# pms.net
KiCad netlist of a schematic drawn in EAGLE
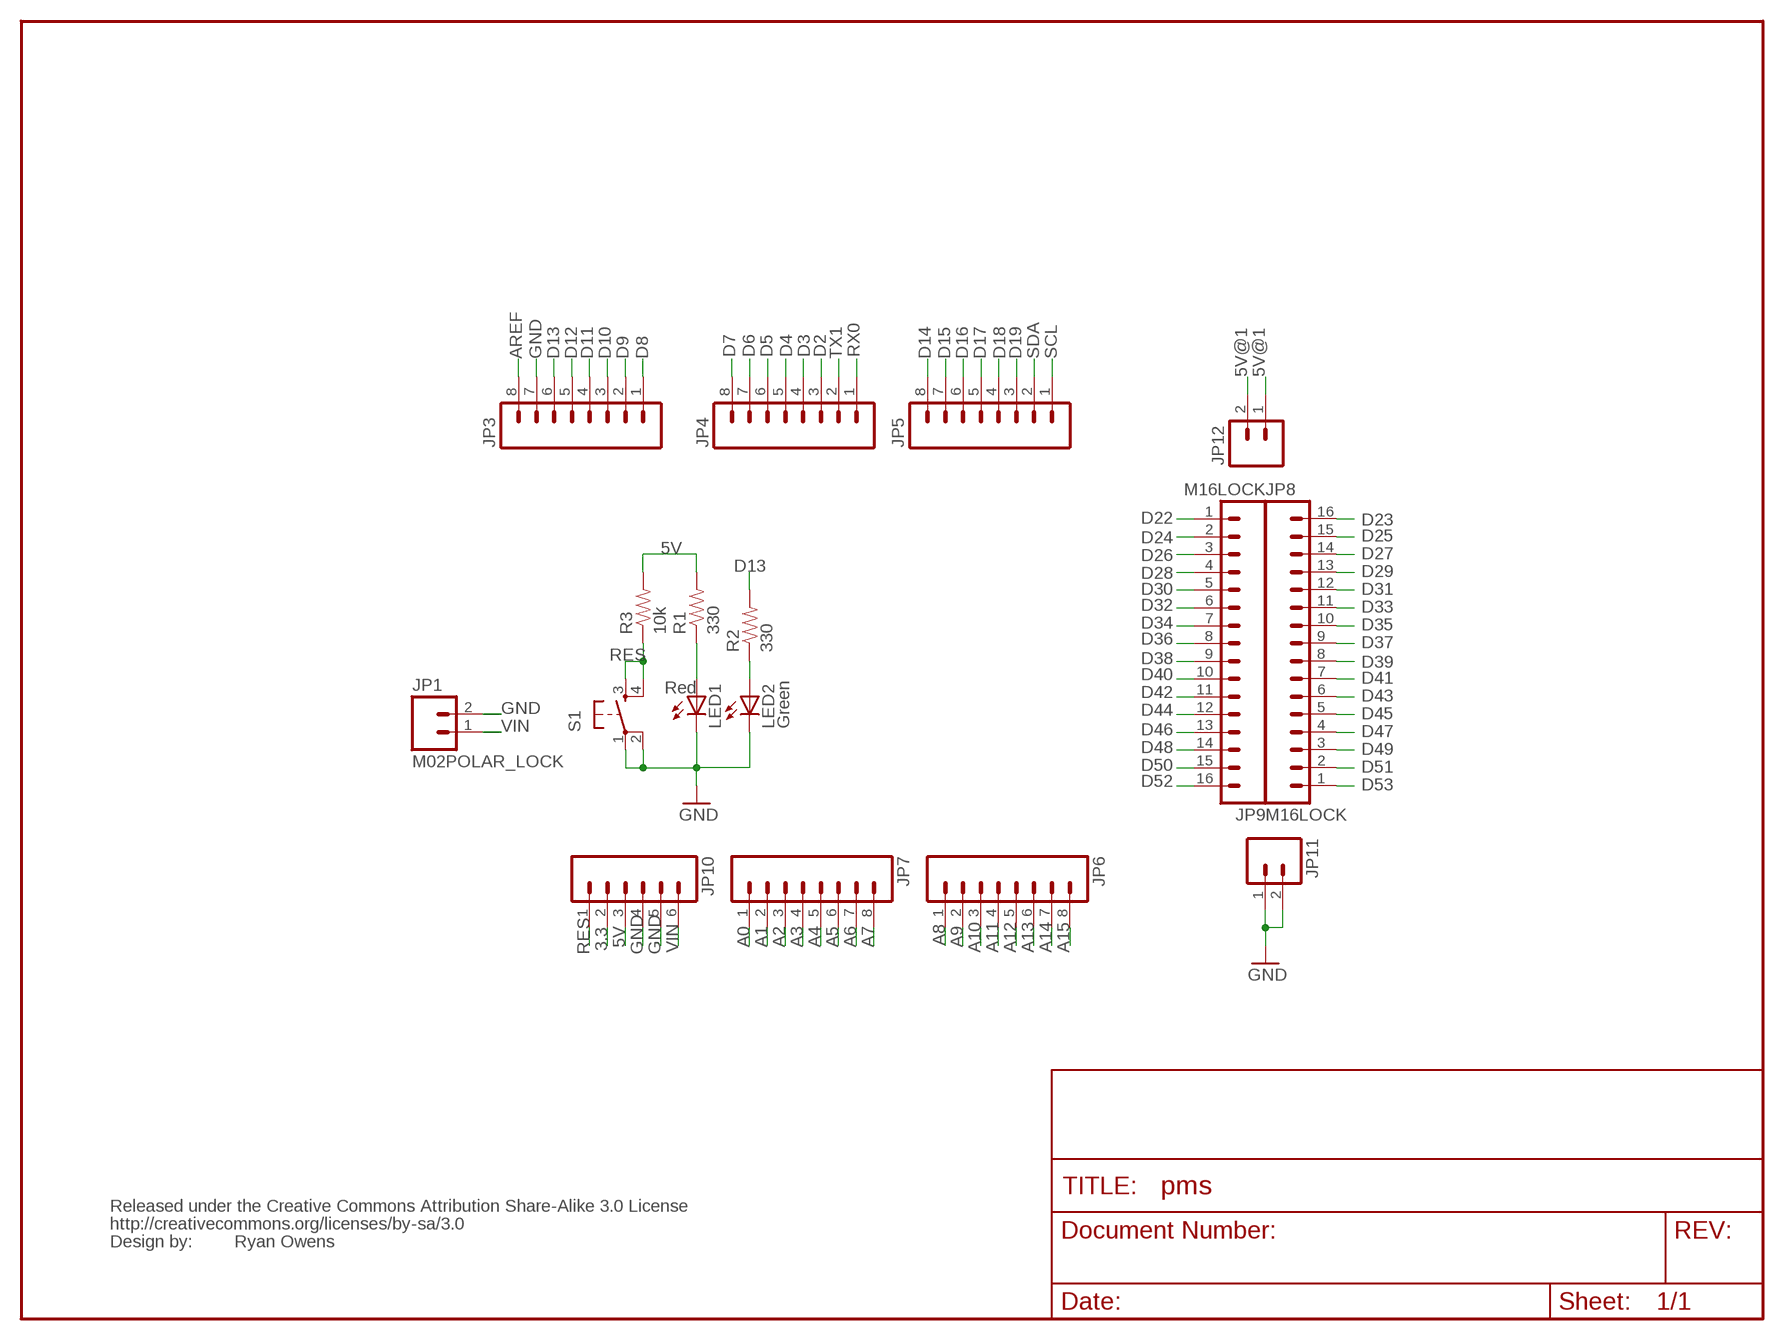
[diagram p0: schematic, sheet 1]

(export (version "E")
  (design (tool "Eeschema 10.0.6"))
  (components
    (comp (ref "JP1")
      (value "M02POLAR_LOCK")
      (footprint "eagle-import:MOLEX-1X2_LOCK")
      (libsource (lib "eagle-import") (part "SparkFun-Connectors_M02POLAR_LOCK"))
    )
    (comp (ref "JP3")
      (value "M08LOCK")
      (footprint "eagle-import:1X08_LOCK")
      (libsource (lib "eagle-import") (part "M08LOCK"))
    )
    (comp (ref "JP4")
      (value "M08LOCK")
      (footprint "eagle-import:1X08_LOCK")
      (libsource (lib "eagle-import") (part "M08LOCK"))
    )
    (comp (ref "JP5")
      (value "M08LOCK")
      (footprint "eagle-import:1X08_LOCK")
      (libsource (lib "eagle-import") (part "M08LOCK"))
    )
    (comp (ref "JP6")
      (value "M08LOCK")
      (footprint "eagle-import:1X08_LOCK")
      (libsource (lib "eagle-import") (part "M08LOCK"))
    )
    (comp (ref "JP7")
      (value "M08LOCK")
      (footprint "eagle-import:1X08_LOCK")
      (libsource (lib "eagle-import") (part "M08LOCK"))
    )
    (comp (ref "JP8")
      (value "M16LOCK")
      (footprint "eagle-import:1X16_LOCK")
      (libsource (lib "eagle-import") (part "M16LOCK"))
    )
    (comp (ref "JP9")
      (value "M16LOCK")
      (footprint "eagle-import:1X16_LOCK")
      (libsource (lib "eagle-import") (part "M16LOCK"))
    )
    (comp (ref "JP10")
      (value "M06LOCK")
      (footprint "eagle-import:1X06_LOCK")
      (libsource (lib "eagle-import") (part "M06LOCK"))
    )
    (comp (ref "JP11")
      (value "M02LOCK")
      (footprint "eagle-import:1X02_LOCK")
      (libsource (lib "eagle-import") (part "M02LOCK"))
    )
    (comp (ref "JP12")
      (value "M02LOCK")
      (footprint "eagle-import:1X02_LOCK")
      (libsource (lib "eagle-import") (part "M02LOCK"))
    )
    (comp (ref "LED1")
      (value "Red")
      (footprint "eagle-import:LED5MM")
      (libsource (lib "eagle-import") (part "LED5MM"))
    )
    (comp (ref "LED2")
      (value "Green")
      (footprint "eagle-import:LED5MM")
      (libsource (lib "eagle-import") (part "LED5MM"))
    )
    (comp (ref "R1")
      (value "330")
      (footprint "eagle-import:AXIAL-0.3")
      (libsource (lib "eagle-import") (part "RESISTORPTH1"))
    )
    (comp (ref "R2")
      (value "330")
      (footprint "eagle-import:AXIAL-0.3")
      (libsource (lib "eagle-import") (part "RESISTORPTH1"))
    )
    (comp (ref "R3")
      (value "10k")
      (footprint "eagle-import:AXIAL-0.3")
      (libsource (lib "eagle-import") (part "RESISTORPTH1"))
    )
    (comp (ref "S1")
      (value "TAC_SWITCHPTH")
      (footprint "eagle-import:TACTILE-PTH")
      (libsource (lib "eagle-import") (part "TAC_SWITCHPTH"))
    )
    (comp (ref "U$2")
      (value "CREATIVE_COMMONS")
      (footprint "eagle-import:CREATIVE_COMMONS")
      (libsource (lib "eagle-import") (part "CREATIVE_COMMONS"))
    )
  )
  (nets
    (net (code "1") (name "/3.3") (class "Default")
      (node (ref "JP10") (pin "2") (pinfunction "2_2") (pintype "passive"))
    )
    (net (code "2") (name "/5V") (class "Default")
      (node (ref "JP10") (pin "3") (pinfunction "3_3") (pintype "passive"))
      (node (ref "R1") (pin "P$2") (pinfunction "2_P$2") (pintype "passive"))
      (node (ref "R3") (pin "P$2") (pinfunction "2_P$2") (pintype "passive"))
    )
    (net (code "3") (name "/5V@1") (class "Default")
      (node (ref "JP12") (pin "1") (pinfunction "1_1") (pintype "passive"))
      (node (ref "JP12") (pin "2") (pinfunction "2_2") (pintype "passive"))
    )
    (net (code "4") (name "/A0") (class "Default")
      (node (ref "JP7") (pin "1") (pinfunction "1_1") (pintype "passive"))
    )
    (net (code "5") (name "/A1") (class "Default")
      (node (ref "JP7") (pin "2") (pinfunction "2_2") (pintype "passive"))
    )
    (net (code "6") (name "/A2") (class "Default")
      (node (ref "JP7") (pin "3") (pinfunction "3_3") (pintype "passive"))
    )
    (net (code "7") (name "/A3") (class "Default")
      (node (ref "JP7") (pin "4") (pinfunction "4_4") (pintype "passive"))
    )
    (net (code "8") (name "/A4") (class "Default")
      (node (ref "JP7") (pin "5") (pinfunction "5_5") (pintype "passive"))
    )
    (net (code "9") (name "/A5") (class "Default")
      (node (ref "JP7") (pin "6") (pinfunction "6_6") (pintype "passive"))
    )
    (net (code "10") (name "/A6") (class "Default")
      (node (ref "JP7") (pin "7") (pinfunction "7_7") (pintype "passive"))
    )
    (net (code "11") (name "/A7") (class "Default")
      (node (ref "JP7") (pin "8") (pinfunction "8_8") (pintype "passive"))
    )
    (net (code "12") (name "/A8") (class "Default")
      (node (ref "JP6") (pin "1") (pinfunction "1_1") (pintype "passive"))
    )
    (net (code "13") (name "/A9") (class "Default")
      (node (ref "JP6") (pin "2") (pinfunction "2_2") (pintype "passive"))
    )
    (net (code "14") (name "/A10") (class "Default")
      (node (ref "JP6") (pin "3") (pinfunction "3_3") (pintype "passive"))
    )
    (net (code "15") (name "/A11") (class "Default")
      (node (ref "JP6") (pin "4") (pinfunction "4_4") (pintype "passive"))
    )
    (net (code "16") (name "/A12") (class "Default")
      (node (ref "JP6") (pin "5") (pinfunction "5_5") (pintype "passive"))
    )
    (net (code "17") (name "/A13") (class "Default")
      (node (ref "JP6") (pin "6") (pinfunction "6_6") (pintype "passive"))
    )
    (net (code "18") (name "/A14") (class "Default")
      (node (ref "JP6") (pin "7") (pinfunction "7_7") (pintype "passive"))
    )
    (net (code "19") (name "/A15") (class "Default")
      (node (ref "JP6") (pin "8") (pinfunction "8_8") (pintype "passive"))
    )
    (net (code "20") (name "/AREF") (class "Default")
      (node (ref "JP3") (pin "8") (pinfunction "8_8") (pintype "passive"))
    )
    (net (code "21") (name "/D2") (class "Default")
      (node (ref "JP4") (pin "3") (pinfunction "3_3") (pintype "passive"))
    )
    (net (code "22") (name "/D3") (class "Default")
      (node (ref "JP4") (pin "4") (pinfunction "4_4") (pintype "passive"))
    )
    (net (code "23") (name "/D4") (class "Default")
      (node (ref "JP4") (pin "5") (pinfunction "5_5") (pintype "passive"))
    )
    (net (code "24") (name "/D5") (class "Default")
      (node (ref "JP4") (pin "6") (pinfunction "6_6") (pintype "passive"))
    )
    (net (code "25") (name "/D6") (class "Default")
      (node (ref "JP4") (pin "7") (pinfunction "7_7") (pintype "passive"))
    )
    (net (code "26") (name "/D7") (class "Default")
      (node (ref "JP4") (pin "8") (pinfunction "8_8") (pintype "passive"))
    )
    (net (code "27") (name "/D8") (class "Default")
      (node (ref "JP3") (pin "1") (pinfunction "1_1") (pintype "passive"))
    )
    (net (code "28") (name "/D9") (class "Default")
      (node (ref "JP3") (pin "2") (pinfunction "2_2") (pintype "passive"))
    )
    (net (code "29") (name "/D10") (class "Default")
      (node (ref "JP3") (pin "3") (pinfunction "3_3") (pintype "passive"))
    )
    (net (code "30") (name "/D11") (class "Default")
      (node (ref "JP3") (pin "4") (pinfunction "4_4") (pintype "passive"))
    )
    (net (code "31") (name "/D12") (class "Default")
      (node (ref "JP3") (pin "5") (pinfunction "5_5") (pintype "passive"))
    )
    (net (code "32") (name "/D13") (class "Default")
      (node (ref "JP3") (pin "6") (pinfunction "6_6") (pintype "passive"))
      (node (ref "R2") (pin "P$2") (pinfunction "2_P$2") (pintype "passive"))
    )
    (net (code "33") (name "/D14") (class "Default")
      (node (ref "JP5") (pin "8") (pinfunction "8_8") (pintype "passive"))
    )
    (net (code "34") (name "/D15") (class "Default")
      (node (ref "JP5") (pin "7") (pinfunction "7_7") (pintype "passive"))
    )
    (net (code "35") (name "/D16") (class "Default")
      (node (ref "JP5") (pin "6") (pinfunction "6_6") (pintype "passive"))
    )
    (net (code "36") (name "/D17") (class "Default")
      (node (ref "JP5") (pin "5") (pinfunction "5_5") (pintype "passive"))
    )
    (net (code "37") (name "/D18") (class "Default")
      (node (ref "JP5") (pin "4") (pinfunction "4_4") (pintype "passive"))
    )
    (net (code "38") (name "/D19") (class "Default")
      (node (ref "JP5") (pin "3") (pinfunction "3_3") (pintype "passive"))
    )
    (net (code "39") (name "/D22") (class "Default")
      (node (ref "JP9") (pin "1") (pinfunction "1_1") (pintype "passive"))
    )
    (net (code "40") (name "/D23") (class "Default")
      (node (ref "JP8") (pin "16") (pinfunction "16_16") (pintype "passive"))
    )
    (net (code "41") (name "/D24") (class "Default")
      (node (ref "JP9") (pin "2") (pinfunction "2_2") (pintype "passive"))
    )
    (net (code "42") (name "/D25") (class "Default")
      (node (ref "JP8") (pin "15") (pinfunction "15_15") (pintype "passive"))
    )
    (net (code "43") (name "/D26") (class "Default")
      (node (ref "JP9") (pin "3") (pinfunction "3_3") (pintype "passive"))
    )
    (net (code "44") (name "/D27") (class "Default")
      (node (ref "JP8") (pin "14") (pinfunction "14_14") (pintype "passive"))
    )
    (net (code "45") (name "/D28") (class "Default")
      (node (ref "JP9") (pin "4") (pinfunction "4_4") (pintype "passive"))
    )
    (net (code "46") (name "/D29") (class "Default")
      (node (ref "JP8") (pin "13") (pinfunction "13_13") (pintype "passive"))
    )
    (net (code "47") (name "/D30") (class "Default")
      (node (ref "JP9") (pin "5") (pinfunction "5_5") (pintype "passive"))
    )
    (net (code "48") (name "/D31") (class "Default")
      (node (ref "JP8") (pin "12") (pinfunction "12_12") (pintype "passive"))
    )
    (net (code "49") (name "/D32") (class "Default")
      (node (ref "JP9") (pin "6") (pinfunction "6_6") (pintype "passive"))
    )
    (net (code "50") (name "/D33") (class "Default")
      (node (ref "JP8") (pin "11") (pinfunction "11_11") (pintype "passive"))
    )
    (net (code "51") (name "/D34") (class "Default")
      (node (ref "JP9") (pin "7") (pinfunction "7_7") (pintype "passive"))
    )
    (net (code "52") (name "/D35") (class "Default")
      (node (ref "JP8") (pin "10") (pinfunction "10_10") (pintype "passive"))
    )
    (net (code "53") (name "/D36") (class "Default")
      (node (ref "JP9") (pin "8") (pinfunction "8_8") (pintype "passive"))
    )
    (net (code "54") (name "/D37") (class "Default")
      (node (ref "JP8") (pin "9") (pinfunction "9_9") (pintype "passive"))
    )
    (net (code "55") (name "/D38") (class "Default")
      (node (ref "JP9") (pin "9") (pinfunction "9_9") (pintype "passive"))
    )
    (net (code "56") (name "/D39") (class "Default")
      (node (ref "JP8") (pin "8") (pinfunction "8_8") (pintype "passive"))
    )
    (net (code "57") (name "/D40") (class "Default")
      (node (ref "JP9") (pin "10") (pinfunction "10_10") (pintype "passive"))
    )
    (net (code "58") (name "/D41") (class "Default")
      (node (ref "JP8") (pin "7") (pinfunction "7_7") (pintype "passive"))
    )
    (net (code "59") (name "/D42") (class "Default")
      (node (ref "JP9") (pin "11") (pinfunction "11_11") (pintype "passive"))
    )
    (net (code "60") (name "/D43") (class "Default")
      (node (ref "JP8") (pin "6") (pinfunction "6_6") (pintype "passive"))
    )
    (net (code "61") (name "/D44") (class "Default")
      (node (ref "JP9") (pin "12") (pinfunction "12_12") (pintype "passive"))
    )
    (net (code "62") (name "/D45") (class "Default")
      (node (ref "JP8") (pin "5") (pinfunction "5_5") (pintype "passive"))
    )
    (net (code "63") (name "/D46") (class "Default")
      (node (ref "JP9") (pin "13") (pinfunction "13_13") (pintype "passive"))
    )
    (net (code "64") (name "/D47") (class "Default")
      (node (ref "JP8") (pin "4") (pinfunction "4_4") (pintype "passive"))
    )
    (net (code "65") (name "/D48") (class "Default")
      (node (ref "JP9") (pin "14") (pinfunction "14_14") (pintype "passive"))
    )
    (net (code "66") (name "/D49") (class "Default")
      (node (ref "JP8") (pin "3") (pinfunction "3_3") (pintype "passive"))
    )
    (net (code "67") (name "/D50") (class "Default")
      (node (ref "JP9") (pin "15") (pinfunction "15_15") (pintype "passive"))
    )
    (net (code "68") (name "/D51") (class "Default")
      (node (ref "JP8") (pin "2") (pinfunction "2_2") (pintype "passive"))
    )
    (net (code "69") (name "/D52") (class "Default")
      (node (ref "JP9") (pin "16") (pinfunction "16_16") (pintype "passive"))
    )
    (net (code "70") (name "/D53") (class "Default")
      (node (ref "JP8") (pin "1") (pinfunction "1_1") (pintype "passive"))
    )
    (net (code "71") (name "/RES") (class "Default")
      (node (ref "JP10") (pin "1") (pinfunction "1_1") (pintype "passive"))
      (node (ref "R3") (pin "P$1") (pinfunction "1_P$1") (pintype "passive"))
      (node (ref "S1") (pin "3") (pinfunction "3_3") (pintype "passive"))
      (node (ref "S1") (pin "4") (pinfunction "4_4") (pintype "passive"))
    )
    (net (code "72") (name "/RX0") (class "Default")
      (node (ref "JP4") (pin "1") (pinfunction "1_1") (pintype "passive"))
    )
    (net (code "73") (name "/SCL") (class "Default")
      (node (ref "JP5") (pin "1") (pinfunction "1_1") (pintype "passive"))
    )
    (net (code "74") (name "/SDA") (class "Default")
      (node (ref "JP5") (pin "2") (pinfunction "2_2") (pintype "passive"))
    )
    (net (code "75") (name "/TX1") (class "Default")
      (node (ref "JP4") (pin "2") (pinfunction "2_2") (pintype "passive"))
    )
    (net (code "76") (name "/VIN") (class "Default")
      (node (ref "JP1") (pin "1") (pinfunction "1_1") (pintype "passive"))
      (node (ref "JP10") (pin "6") (pinfunction "6_6") (pintype "passive"))
    )
    (net (code "77") (name "GND") (class "Default")
      (node (ref "JP1") (pin "2") (pinfunction "2_2") (pintype "passive"))
      (node (ref "JP10") (pin "4") (pinfunction "4_4") (pintype "passive"))
      (node (ref "JP10") (pin "5") (pinfunction "5_5") (pintype "passive"))
      (node (ref "JP11") (pin "1") (pinfunction "1_1") (pintype "passive"))
      (node (ref "JP11") (pin "2") (pinfunction "2_2") (pintype "passive"))
      (node (ref "JP3") (pin "7") (pinfunction "7_7") (pintype "passive"))
      (node (ref "LED1") (pin "K") (pinfunction "C_K") (pintype "passive"))
      (node (ref "LED2") (pin "K") (pinfunction "C_K") (pintype "passive"))
      (node (ref "S1") (pin "1") (pinfunction "1_1") (pintype "passive"))
      (node (ref "S1") (pin "2") (pinfunction "2_2") (pintype "passive"))
    )
    (net (code "78") (name "Net-(R1-1)") (class "Default")
      (node (ref "LED1") (pin "A") (pinfunction "A_A") (pintype "passive"))
      (node (ref "R1") (pin "P$1") (pinfunction "1_P$1") (pintype "passive"))
    )
    (net (code "79") (name "Net-(R2-1)") (class "Default")
      (node (ref "LED2") (pin "A") (pinfunction "A_A") (pintype "passive"))
      (node (ref "R2") (pin "P$1") (pinfunction "1_P$1") (pintype "passive"))
    )
  )
)
